# V_7.net
KiCad netlist of a schematic drawn in Altium Designer
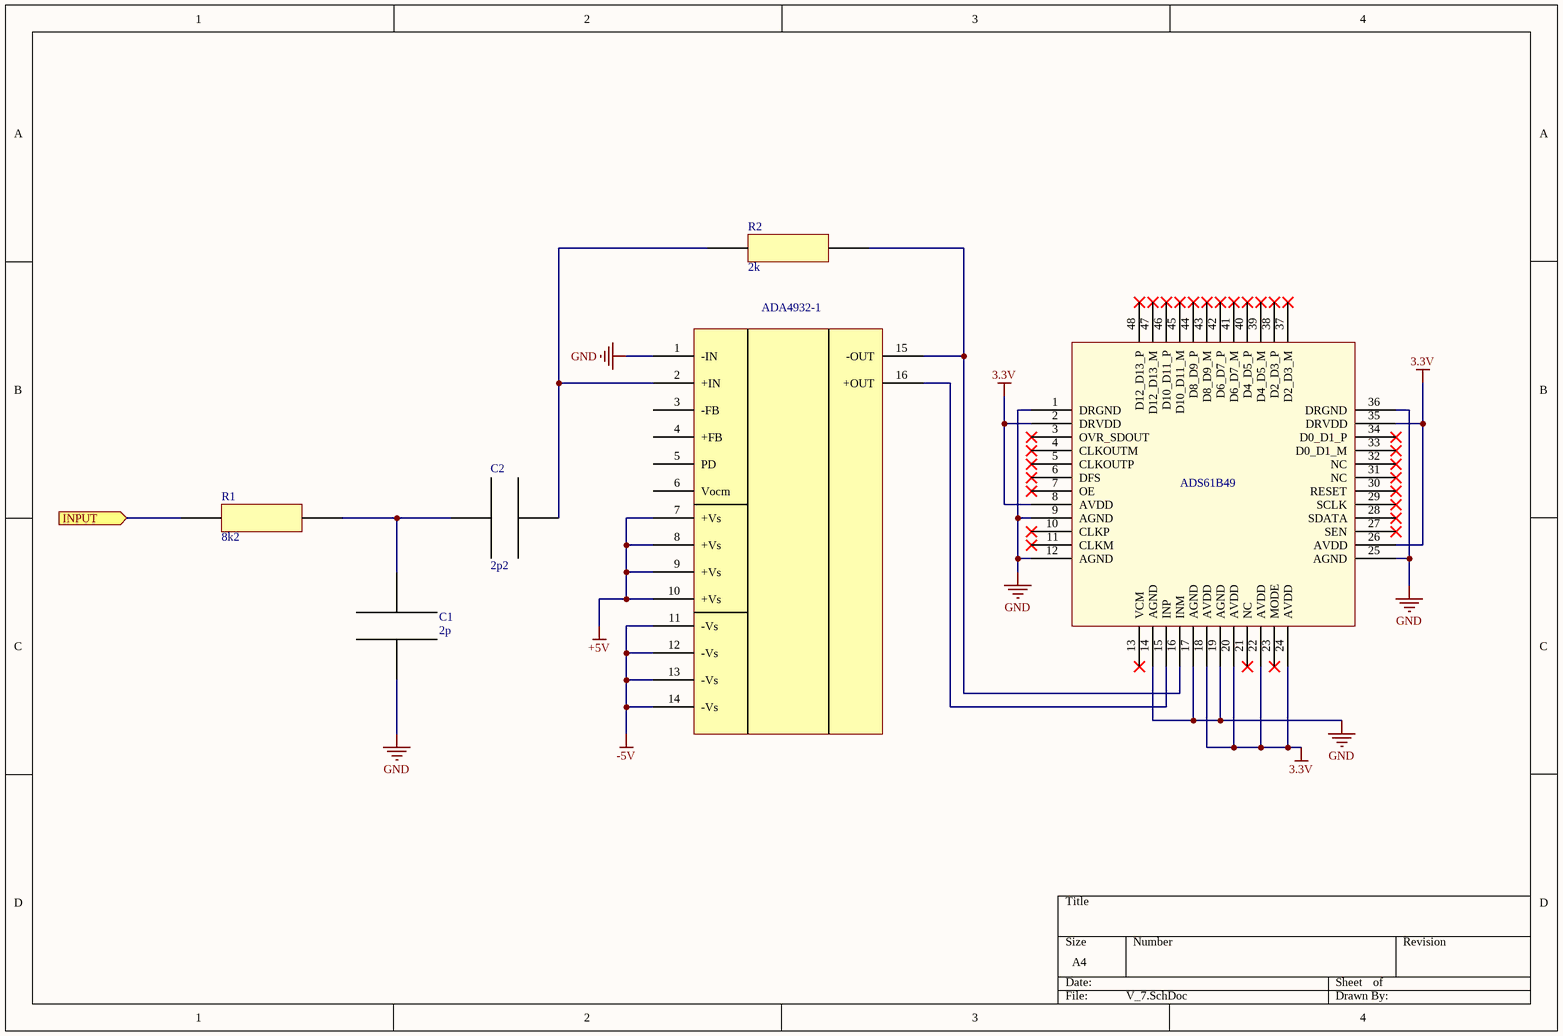
[diagram p0: V_7.SchDoc]

(export (version "E")
  (design (tool "Eeschema 10.0.6"))
  (components
    (comp (ref "1") (value "ADA4932-1") (footprint "ADA4932-1") (libsource (lib "V_7") (part "ADA4932-1")))
    (comp (ref "2") (value "ADS61B49") (footprint "ADS61B49") (libsource (lib "V_7") (part "ADS61B49")))
    (comp (ref "C1") (value "2p") (footprint "SMD") (libsource (lib "V_7") (part "CAP")))
    (comp (ref "C2") (value "2p2") (footprint "SMD") (libsource (lib "V_7") (part "CAP")))
    (comp (ref "R1") (value "8k2") (footprint "SMD") (libsource (lib "V_7") (part "RES")))
    (comp (ref "R2") (value "2k") (footprint "SMD") (libsource (lib "V_7") (part "RES")))
  )
  (nets
    (net (code "1") (name "+5V") (class "Default")
      (node (ref "1") (pin "10") (pinfunction "+Vs_10") (pintype "passive"))
      (node (ref "1") (pin "7") (pinfunction "+Vs_7") (pintype "passive"))
      (node (ref "1") (pin "8") (pinfunction "+Vs_8") (pintype "passive"))
      (node (ref "1") (pin "9") (pinfunction "+Vs_9") (pintype "passive"))
    )
    (net (code "2") (name "-5V") (class "Default")
      (node (ref "1") (pin "11") (pinfunction "-Vs_11") (pintype "passive"))
      (node (ref "1") (pin "12") (pinfunction "-Vs_12") (pintype "passive"))
      (node (ref "1") (pin "13") (pinfunction "-Vs_13") (pintype "passive"))
      (node (ref "1") (pin "14") (pinfunction "-Vs_14") (pintype "passive"))
    )
    (net (code "3") (name "/INPUT") (class "Default")
      (node (ref "R1") (pin "1") (pinfunction "1_1") (pintype "passive"))
    )
    (net (code "4") (name "3.3V") (class "Default")
      (node (ref "2") (pin "18") (pinfunction "AVDD_18") (pintype "passive"))
      (node (ref "2") (pin "2") (pinfunction "DRVDD_2") (pintype "passive"))
      (node (ref "2") (pin "20") (pinfunction "AVDD_20") (pintype "passive"))
      (node (ref "2") (pin "22") (pinfunction "AVDD_22") (pintype "passive"))
      (node (ref "2") (pin "24") (pinfunction "AVDD_24") (pintype "passive"))
      (node (ref "2") (pin "26") (pinfunction "AVDD_26") (pintype "passive"))
      (node (ref "2") (pin "35") (pinfunction "DRVDD_35") (pintype "passive"))
      (node (ref "2") (pin "8") (pinfunction "AVDD_8") (pintype "passive"))
    )
    (net (code "5") (name "GND") (class "Default")
      (node (ref "1") (pin "1") (pinfunction "-IN_1") (pintype "passive"))
      (node (ref "2") (pin "1") (pinfunction "DRGND_1") (pintype "passive"))
      (node (ref "2") (pin "12") (pinfunction "AGND_12") (pintype "passive"))
      (node (ref "2") (pin "14") (pinfunction "AGND_14") (pintype "passive"))
      (node (ref "2") (pin "17") (pinfunction "AGND_17") (pintype "passive"))
      (node (ref "2") (pin "19") (pinfunction "AGND_19") (pintype "passive"))
      (node (ref "2") (pin "25") (pinfunction "AGND_25") (pintype "passive"))
      (node (ref "2") (pin "36") (pinfunction "DRGND_36") (pintype "passive"))
      (node (ref "2") (pin "9") (pinfunction "AGND_9") (pintype "passive"))
      (node (ref "C1") (pin "1") (pinfunction "1_1") (pintype "passive"))
    )
    (net (code "6") (name "Net-(1-+IN)") (class "Default")
      (node (ref "1") (pin "2") (pinfunction "+IN_2") (pintype "passive"))
      (node (ref "C2") (pin "2") (pinfunction "2_2") (pintype "passive"))
      (node (ref "R2") (pin "1") (pinfunction "1_1") (pintype "passive"))
    )
    (net (code "7") (name "Net-(1-+OUT)") (class "Default")
      (node (ref "1") (pin "16") (pinfunction "+OUT_16") (pintype "passive"))
      (node (ref "2") (pin "15") (pinfunction "INP_15") (pintype "passive"))
    )
    (net (code "8") (name "Net-(1--OUT)") (class "Default")
      (node (ref "1") (pin "15") (pinfunction "-OUT_15") (pintype "passive"))
      (node (ref "2") (pin "16") (pinfunction "INM_16") (pintype "passive"))
      (node (ref "R2") (pin "2") (pinfunction "2_2") (pintype "passive"))
    )
    (net (code "9") (name "Net-(C1-Pad2)") (class "Default")
      (node (ref "C1") (pin "2") (pinfunction "2_2") (pintype "passive"))
      (node (ref "C2") (pin "1") (pinfunction "1_1") (pintype "passive"))
      (node (ref "R1") (pin "2") (pinfunction "2_2") (pintype "passive"))
    )
    (net (code "10") (name "unconnected-(1-+FB-Pad4)") (class "Default")
      (node (ref "1") (pin "4") (pinfunction "+FB_4") (pintype "passive"))
    )
    (net (code "11") (name "unconnected-(1--FB-Pad3)") (class "Default")
      (node (ref "1") (pin "3") (pinfunction "-FB_3") (pintype "passive"))
    )
    (net (code "12") (name "unconnected-(1-PD-Pad5)") (class "Default")
      (node (ref "1") (pin "5") (pinfunction "PD_5") (pintype "passive"))
    )
    (net (code "13") (name "unconnected-(1-Vocm-Pad6)") (class "Default")
      (node (ref "1") (pin "6") (pinfunction "Vocm_6") (pintype "passive"))
    )
    (net (code "14") (name "unconnected-(2-CLKM-Pad11)") (class "Default")
      (node (ref "2") (pin "11") (pinfunction "CLKM_11") (pintype "passive+no_connect"))
    )
    (net (code "15") (name "unconnected-(2-CLKOUTM-Pad4)") (class "Default")
      (node (ref "2") (pin "4") (pinfunction "CLKOUTM_4") (pintype "passive+no_connect"))
    )
    (net (code "16") (name "unconnected-(2-CLKOUTP-Pad5)") (class "Default")
      (node (ref "2") (pin "5") (pinfunction "CLKOUTP_5") (pintype "passive+no_connect"))
    )
    (net (code "17") (name "unconnected-(2-CLKP-Pad10)") (class "Default")
      (node (ref "2") (pin "10") (pinfunction "CLKP_10") (pintype "passive+no_connect"))
    )
    (net (code "18") (name "unconnected-(2-D0_D1_M-Pad33)") (class "Default")
      (node (ref "2") (pin "33") (pinfunction "D0_D1_M_33") (pintype "passive+no_connect"))
    )
    (net (code "19") (name "unconnected-(2-D0_D1_P-Pad34)") (class "Default")
      (node (ref "2") (pin "34") (pinfunction "D0_D1_P_34") (pintype "passive+no_connect"))
    )
    (net (code "20") (name "unconnected-(2-D2_D3_M-Pad37)") (class "Default")
      (node (ref "2") (pin "37") (pinfunction "D2_D3_M_37") (pintype "passive+no_connect"))
    )
    (net (code "21") (name "unconnected-(2-D2_D3_P-Pad38)") (class "Default")
      (node (ref "2") (pin "38") (pinfunction "D2_D3_P_38") (pintype "passive+no_connect"))
    )
    (net (code "22") (name "unconnected-(2-D4_D5_M-Pad39)") (class "Default")
      (node (ref "2") (pin "39") (pinfunction "D4_D5_M_39") (pintype "passive+no_connect"))
    )
    (net (code "23") (name "unconnected-(2-D4_D5_P-Pad40)") (class "Default")
      (node (ref "2") (pin "40") (pinfunction "D4_D5_P_40") (pintype "passive+no_connect"))
    )
    (net (code "24") (name "unconnected-(2-D6_D7_M-Pad41)") (class "Default")
      (node (ref "2") (pin "41") (pinfunction "D6_D7_M_41") (pintype "passive+no_connect"))
    )
    (net (code "25") (name "unconnected-(2-D6_D7_P-Pad42)") (class "Default")
      (node (ref "2") (pin "42") (pinfunction "D6_D7_P_42") (pintype "passive+no_connect"))
    )
    (net (code "26") (name "unconnected-(2-D8_D9_M-Pad43)") (class "Default")
      (node (ref "2") (pin "43") (pinfunction "D8_D9_M_43") (pintype "passive+no_connect"))
    )
    (net (code "27") (name "unconnected-(2-D8_D9_P-Pad44)") (class "Default")
      (node (ref "2") (pin "44") (pinfunction "D8_D9_P_44") (pintype "passive+no_connect"))
    )
    (net (code "28") (name "unconnected-(2-D10_D11_M-Pad45)") (class "Default")
      (node (ref "2") (pin "45") (pinfunction "D10_D11_M_45") (pintype "passive+no_connect"))
    )
    (net (code "29") (name "unconnected-(2-D10_D11_P-Pad46)") (class "Default")
      (node (ref "2") (pin "46") (pinfunction "D10_D11_P_46") (pintype "passive+no_connect"))
    )
    (net (code "30") (name "unconnected-(2-D12_D13_M-Pad47)") (class "Default")
      (node (ref "2") (pin "47") (pinfunction "D12_D13_M_47") (pintype "passive+no_connect"))
    )
    (net (code "31") (name "unconnected-(2-D12_D13_P-Pad48)") (class "Default")
      (node (ref "2") (pin "48") (pinfunction "D12_D13_P_48") (pintype "passive+no_connect"))
    )
    (net (code "32") (name "unconnected-(2-DFS-Pad6)") (class "Default")
      (node (ref "2") (pin "6") (pinfunction "DFS_6") (pintype "passive+no_connect"))
    )
    (net (code "33") (name "unconnected-(2-MODE-Pad23)") (class "Default")
      (node (ref "2") (pin "23") (pinfunction "MODE_23") (pintype "passive+no_connect"))
    )
    (net (code "34") (name "unconnected-(2-NC-Pad21)") (class "Default")
      (node (ref "2") (pin "21") (pinfunction "NC_21") (pintype "passive+no_connect"))
    )
    (net (code "35") (name "unconnected-(2-NC-Pad31)") (class "Default")
      (node (ref "2") (pin "31") (pinfunction "NC_31") (pintype "passive+no_connect"))
    )
    (net (code "36") (name "unconnected-(2-NC-Pad32)") (class "Default")
      (node (ref "2") (pin "32") (pinfunction "NC_32") (pintype "passive+no_connect"))
    )
    (net (code "37") (name "unconnected-(2-OE-Pad7)") (class "Default")
      (node (ref "2") (pin "7") (pinfunction "OE_7") (pintype "passive+no_connect"))
    )
    (net (code "38") (name "unconnected-(2-OVR_SDOUT-Pad3)") (class "Default")
      (node (ref "2") (pin "3") (pinfunction "OVR_SDOUT_3") (pintype "passive+no_connect"))
    )
    (net (code "39") (name "unconnected-(2-RESET-Pad30)") (class "Default")
      (node (ref "2") (pin "30") (pinfunction "RESET_30") (pintype "passive+no_connect"))
    )
    (net (code "40") (name "unconnected-(2-SCLK-Pad29)") (class "Default")
      (node (ref "2") (pin "29") (pinfunction "SCLK_29") (pintype "passive+no_connect"))
    )
    (net (code "41") (name "unconnected-(2-SDATA-Pad28)") (class "Default")
      (node (ref "2") (pin "28") (pinfunction "SDATA_28") (pintype "passive+no_connect"))
    )
    (net (code "42") (name "unconnected-(2-SEN-Pad27)") (class "Default")
      (node (ref "2") (pin "27") (pinfunction "SEN_27") (pintype "passive+no_connect"))
    )
    (net (code "43") (name "unconnected-(2-VCM-Pad13)") (class "Default")
      (node (ref "2") (pin "13") (pinfunction "VCM_13") (pintype "passive+no_connect"))
    )
  )
)
